# bouton.net
KiCad netlist of a schematic drawn in EAGLE
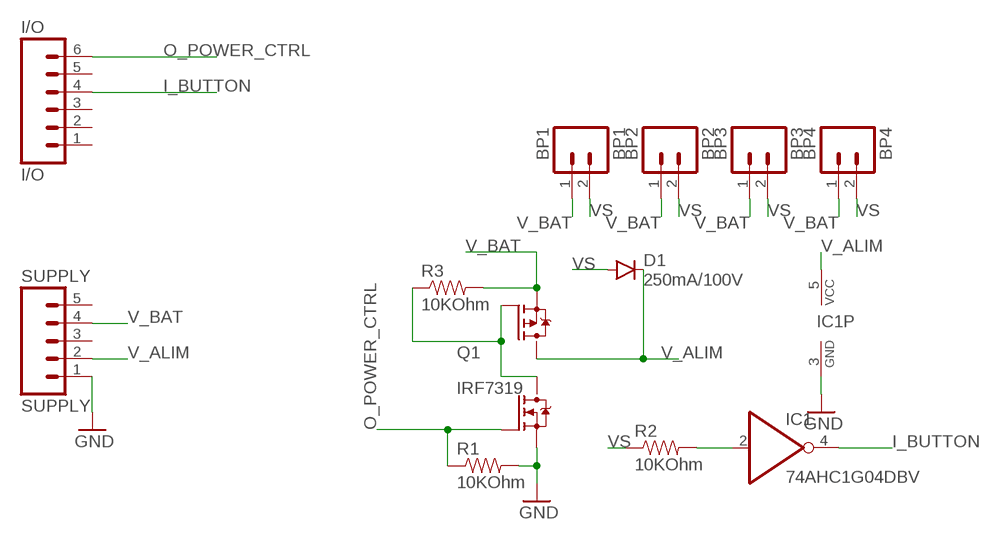
[diagram p0: schematic, sheet 1]

(export (version "E")
  (design (tool "Eeschema 10.0.6"))
  (components
    (comp (ref "BP1")
      (value "BP1")
      (footprint "eagle-import:1X02_NO_SILK")
      (libsource (lib "eagle-import") (part "M021X02_NO_SILK"))
    )
    (comp (ref "BP2")
      (value "BP2")
      (footprint "eagle-import:1X02_NO_SILK")
      (libsource (lib "eagle-import") (part "M021X02_NO_SILK"))
    )
    (comp (ref "BP3")
      (value "BP3")
      (footprint "eagle-import:1X02_NO_SILK")
      (libsource (lib "eagle-import") (part "M021X02_NO_SILK"))
    )
    (comp (ref "BP4")
      (value "BP4")
      (footprint "eagle-import:1X02_NO_SILK")
      (libsource (lib "eagle-import") (part "M021X02_NO_SILK"))
    )
    (comp (ref "D1")
      (value "250mA/100V")
      (footprint "eagle-import:SOD-323")
      (libsource (lib "eagle-import") (part "DIODEBAS16"))
    )
    (comp (ref "I/O")
      (value "I/O")
      (footprint "eagle-import:1X06_NO_SILK")
      (libsource (lib "eagle-import") (part "M06NO_SILK_FEMALE_PTH"))
    )
    (comp (ref "IC1")
      (value "74AHC1G04DBV")
      (footprint "eagle-import:SOT23-5")
      (libsource (lib "eagle-import") (part "741G04DBVAHC"))
    )
    (comp (ref "Q1")
      (value "IRF7319")
      (footprint "eagle-import:SO08-IRF")
      (libsource (lib "eagle-import") (part "IRF7319"))
    )
    (comp (ref "R1")
      (value "10KOhm")
      (footprint "eagle-import:0805")
      (libsource (lib "eagle-import") (part "RESISTOR0805-RES"))
    )
    (comp (ref "R2")
      (value "10KOhm")
      (footprint "eagle-import:0805")
      (libsource (lib "eagle-import") (part "RESISTOR0805-RES"))
    )
    (comp (ref "R3")
      (value "10KOhm")
      (footprint "eagle-import:0805")
      (libsource (lib "eagle-import") (part "RESISTOR0805-RES"))
    )
    (comp (ref "SUPPLY")
      (value "SUPPLY")
      (footprint "eagle-import:1X05_NO_SILK")
      (libsource (lib "eagle-import") (part "M05NO_SILK"))
    )
  )
  (nets
    (net (code "1") (name "/I_BUTTON") (class "Default")
      (node (ref "I/O") (pin "4") (pinfunction "4_4") (pintype "passive"))
      (node (ref "IC1") (pin "4") (pinfunction "O_4") (pintype "output"))
    )
    (net (code "2") (name "/O_POWER_CTRL") (class "Default")
      (node (ref "I/O") (pin "6") (pinfunction "6_6") (pintype "passive"))
      (node (ref "Q1") (pin "2") (pinfunction "N-G_2") (pintype "passive"))
      (node (ref "R1") (pin "1") (pinfunction "1_1") (pintype "passive"))
    )
    (net (code "3") (name "/VS") (class "Default")
      (node (ref "BP1") (pin "2") (pinfunction "2_2") (pintype "passive"))
      (node (ref "BP2") (pin "2") (pinfunction "2_2") (pintype "passive"))
      (node (ref "BP3") (pin "2") (pinfunction "2_2") (pintype "passive"))
      (node (ref "BP4") (pin "2") (pinfunction "2_2") (pintype "passive"))
      (node (ref "D1") (pin "A") (pinfunction "A_A") (pintype "passive"))
      (node (ref "R2") (pin "1") (pinfunction "1_1") (pintype "passive"))
    )
    (net (code "4") (name "/V_ALIM") (class "Default")
      (node (ref "D1") (pin "C") (pinfunction "C_C") (pintype "passive"))
      (node (ref "IC1") (pin "5") (pinfunction "VCC_5") (pintype "power_in"))
      (node (ref "Q1") (pin "5") (pinfunction "P-D_5") (pintype "passive"))
      (node (ref "Q1") (pin "6") (pinfunction "P-D_6") (pintype "passive"))
      (node (ref "SUPPLY") (pin "2") (pinfunction "2_2") (pintype "passive"))
    )
    (net (code "5") (name "/V_BAT") (class "Default")
      (node (ref "BP1") (pin "1") (pinfunction "1_1") (pintype "passive"))
      (node (ref "BP2") (pin "1") (pinfunction "1_1") (pintype "passive"))
      (node (ref "BP3") (pin "1") (pinfunction "1_1") (pintype "passive"))
      (node (ref "BP4") (pin "1") (pinfunction "1_1") (pintype "passive"))
      (node (ref "Q1") (pin "3") (pinfunction "P-S_3") (pintype "passive"))
      (node (ref "R3") (pin "2") (pinfunction "2_2") (pintype "passive"))
      (node (ref "SUPPLY") (pin "4") (pinfunction "4_4") (pintype "passive"))
    )
    (net (code "6") (name "GND") (class "Default")
      (node (ref "IC1") (pin "3") (pinfunction "GND_3") (pintype "power_in"))
      (node (ref "Q1") (pin "1") (pinfunction "N-S_1") (pintype "passive"))
      (node (ref "R1") (pin "2") (pinfunction "2_2") (pintype "passive"))
      (node (ref "SUPPLY") (pin "1") (pinfunction "1_1") (pintype "passive"))
    )
    (net (code "7") (name "Net-(IC1A-I)") (class "Default")
      (node (ref "IC1") (pin "2") (pinfunction "I_2") (pintype "input"))
      (node (ref "R2") (pin "2") (pinfunction "2_2") (pintype "passive"))
    )
    (net (code "8") (name "Net-(Q1-P-G)") (class "Default")
      (node (ref "Q1") (pin "4") (pinfunction "P-G_4") (pintype "passive"))
      (node (ref "Q1") (pin "7") (pinfunction "N-D_7") (pintype "passive"))
      (node (ref "Q1") (pin "8") (pinfunction "N-D_8") (pintype "passive"))
      (node (ref "R3") (pin "1") (pinfunction "1_1") (pintype "passive"))
    )
    (net (code "9") (name "unconnected-(I/O-Pad1)") (class "Default")
      (node (ref "I/O") (pin "1") (pinfunction "1_1") (pintype "passive"))
    )
    (net (code "10") (name "unconnected-(I/O-Pad2)") (class "Default")
      (node (ref "I/O") (pin "2") (pinfunction "2_2") (pintype "passive"))
    )
    (net (code "11") (name "unconnected-(I/O-Pad3)") (class "Default")
      (node (ref "I/O") (pin "3") (pinfunction "3_3") (pintype "passive"))
    )
    (net (code "12") (name "unconnected-(I/O-Pad5)") (class "Default")
      (node (ref "I/O") (pin "5") (pinfunction "5_5") (pintype "passive"))
    )
    (net (code "13") (name "unconnected-(SUPPLY-Pad3)") (class "Default")
      (node (ref "SUPPLY") (pin "3") (pinfunction "3_3") (pintype "passive"))
    )
    (net (code "14") (name "unconnected-(SUPPLY-Pad5)") (class "Default")
      (node (ref "SUPPLY") (pin "5") (pinfunction "5_5") (pintype "passive"))
    )
  )
)
